# M109X.net
KiCad netlist of a schematic drawn in EAGLE
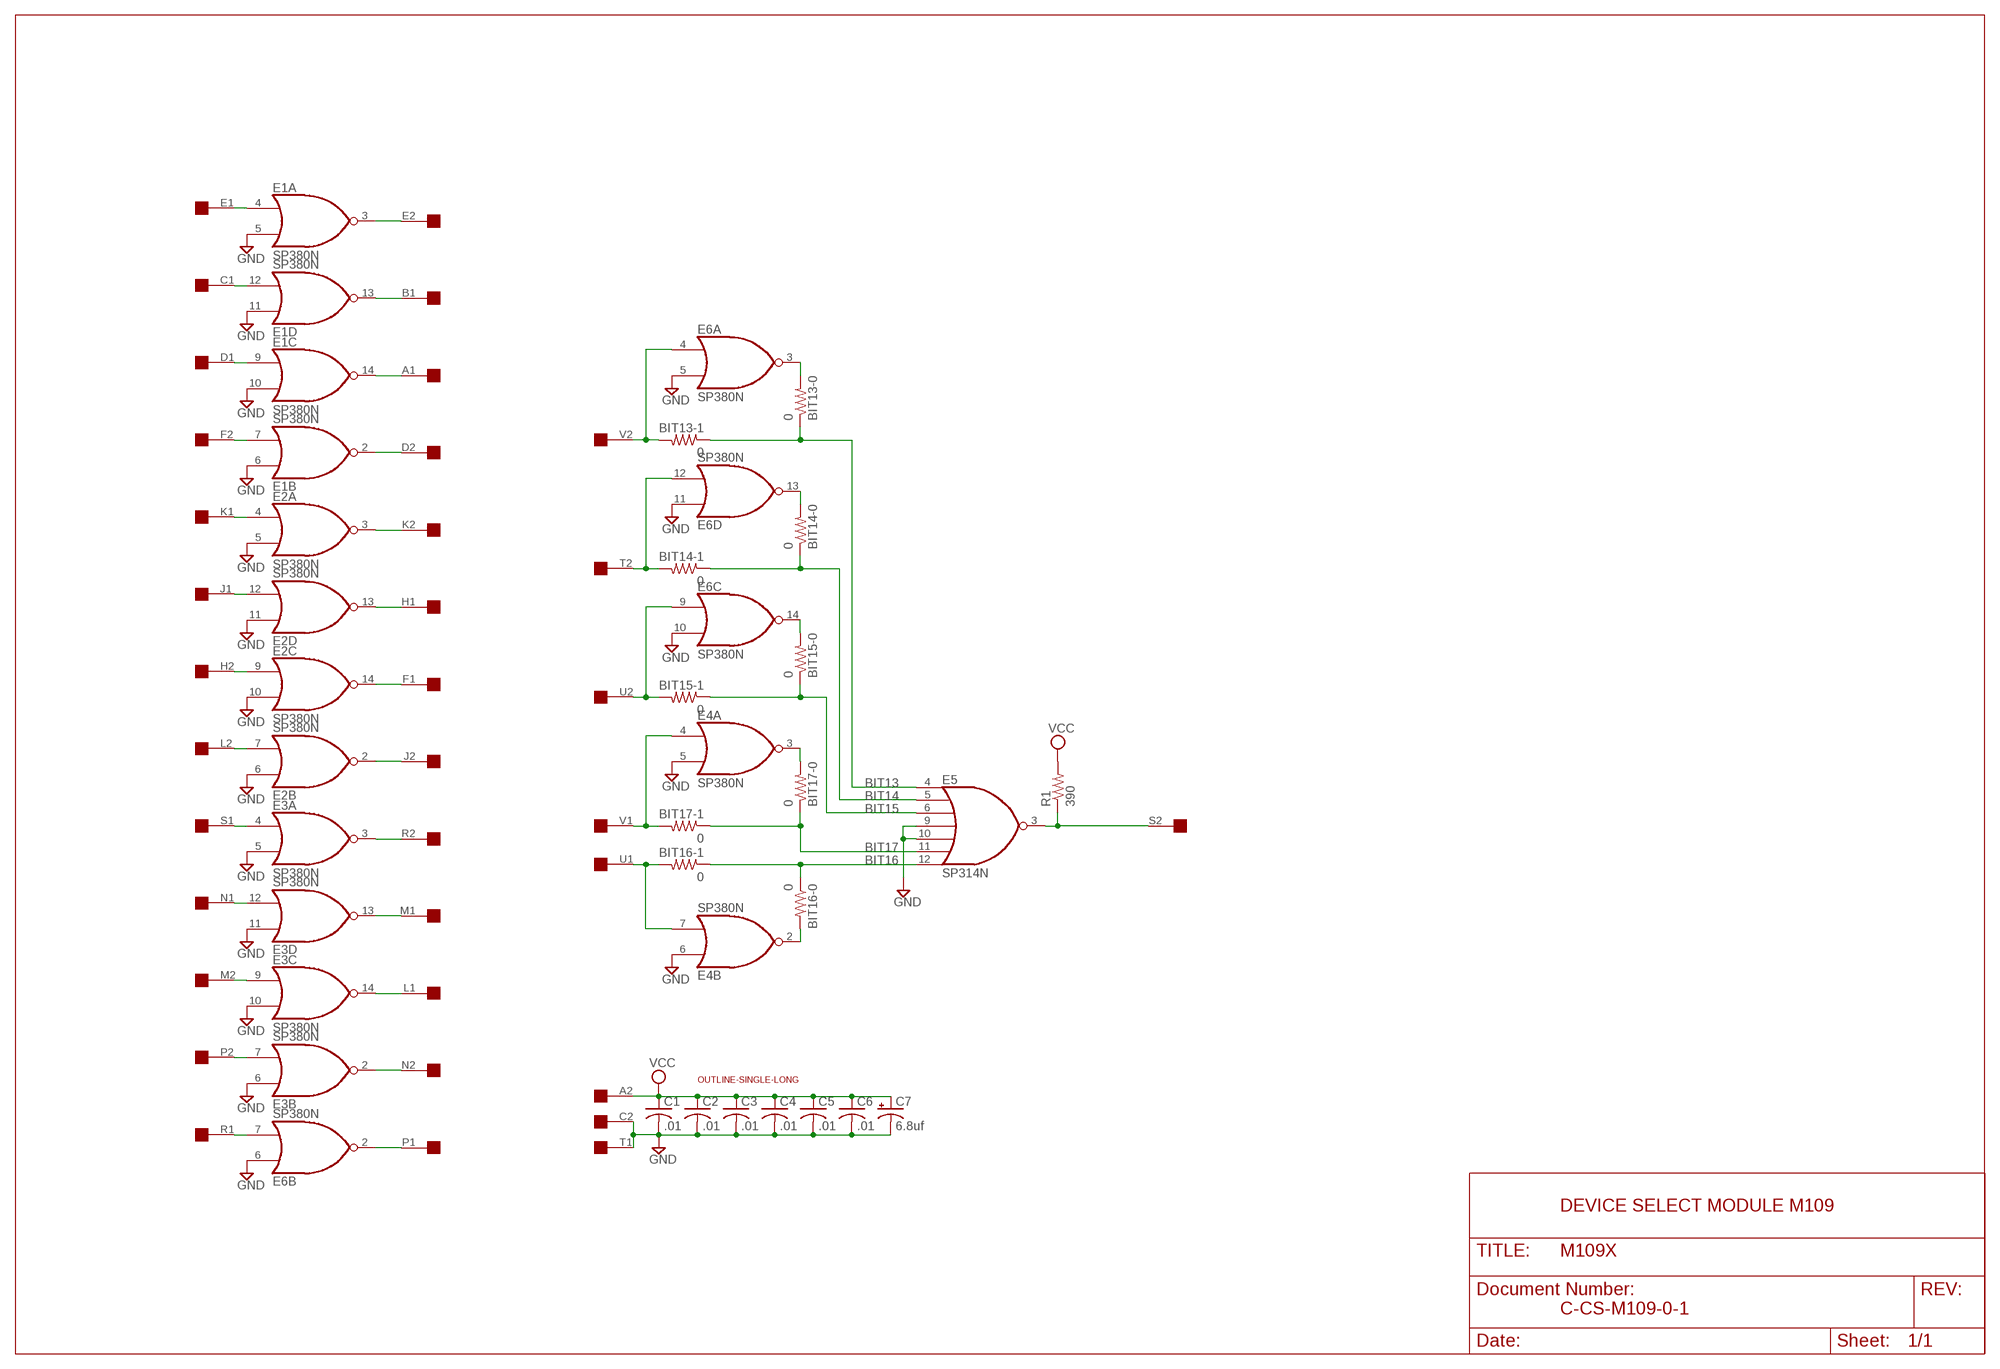
[diagram p0: schematic, sheet 1]

(export (version "E")
  (design (tool "Eeschema 10.0.6"))
  (components
    (comp (ref "BIT13-0")
      (value "0")
      (footprint "eagle-import:0207_10")
      (libsource (lib "eagle-import") (part "R-US_0207/10"))
    )
    (comp (ref "BIT13-1")
      (value "0")
      (footprint "eagle-import:0207_10")
      (libsource (lib "eagle-import") (part "R-US_0207/10"))
    )
    (comp (ref "BIT14-0")
      (value "0")
      (footprint "eagle-import:0207_10")
      (libsource (lib "eagle-import") (part "R-US_0207/10"))
    )
    (comp (ref "BIT14-1")
      (value "0")
      (footprint "eagle-import:0207_10")
      (libsource (lib "eagle-import") (part "R-US_0207/10"))
    )
    (comp (ref "BIT15-0")
      (value "0")
      (footprint "eagle-import:0207_10")
      (libsource (lib "eagle-import") (part "R-US_0207/10"))
    )
    (comp (ref "BIT15-1")
      (value "0")
      (footprint "eagle-import:0207_10")
      (libsource (lib "eagle-import") (part "R-US_0207/10"))
    )
    (comp (ref "BIT16-0")
      (value "0")
      (footprint "eagle-import:0207_10")
      (libsource (lib "eagle-import") (part "R-US_0207/10"))
    )
    (comp (ref "BIT16-1")
      (value "0")
      (footprint "eagle-import:0207_10")
      (libsource (lib "eagle-import") (part "R-US_0207/10"))
    )
    (comp (ref "BIT17-0")
      (value "0")
      (footprint "eagle-import:0207_10")
      (libsource (lib "eagle-import") (part "R-US_0207/10"))
    )
    (comp (ref "BIT17-1")
      (value "0")
      (footprint "eagle-import:0207_10")
      (libsource (lib "eagle-import") (part "R-US_0207/10"))
    )
    (comp (ref "C1")
      (value ".01")
      (footprint "eagle-import:C050-025X075")
      (libsource (lib "eagle-import") (part "C-US050-025X075"))
    )
    (comp (ref "C2")
      (value ".01")
      (footprint "eagle-import:C050-025X075")
      (libsource (lib "eagle-import") (part "C-US050-025X075"))
    )
    (comp (ref "C3")
      (value ".01")
      (footprint "eagle-import:C050-025X075")
      (libsource (lib "eagle-import") (part "C-US050-025X075"))
    )
    (comp (ref "C4")
      (value ".01")
      (footprint "eagle-import:C050-025X075")
      (libsource (lib "eagle-import") (part "C-US050-025X075"))
    )
    (comp (ref "C5")
      (value ".01")
      (footprint "eagle-import:C050-025X075")
      (libsource (lib "eagle-import") (part "C-US050-025X075"))
    )
    (comp (ref "C6")
      (value ".01")
      (footprint "eagle-import:C050-025X075")
      (libsource (lib "eagle-import") (part "C-US050-025X075"))
    )
    (comp (ref "C7")
      (value "6.8uf")
      (footprint "eagle-import:E22-6")
      (libsource (lib "eagle-import") (part "CPOL-USE22-6AXIAL"))
    )
    (comp (ref "E1")
      (value "SP380N")
      (footprint "eagle-import:DIL14")
      (libsource (lib "eagle-import") (part "SP380N"))
    )
    (comp (ref "E2")
      (value "SP380N")
      (footprint "eagle-import:DIL14")
      (libsource (lib "eagle-import") (part "SP380N"))
    )
    (comp (ref "E3")
      (value "SP380N")
      (footprint "eagle-import:DIL14")
      (libsource (lib "eagle-import") (part "SP380N"))
    )
    (comp (ref "E4")
      (value "SP380N")
      (footprint "eagle-import:DIL14")
      (libsource (lib "eagle-import") (part "SP380N"))
    )
    (comp (ref "E5")
      (value "SP314N")
      (footprint "eagle-import:DIL14")
      (libsource (lib "eagle-import") (part "SP314N"))
    )
    (comp (ref "E6")
      (value "SP380N")
      (footprint "eagle-import:DIL14")
      (libsource (lib "eagle-import") (part "SP380N"))
    )
    (comp (ref "R1")
      (value "390")
      (footprint "eagle-import:0207_10")
      (libsource (lib "eagle-import") (part "R-US_0207/10"))
    )
    (comp (ref "U$1")
      (value "SINGLE")
      (footprint "eagle-import:EDGE-CON2")
      (libsource (lib "eagle-import") (part "SINGLE"))
    )
    (comp (ref "U$2")
      (value "OUTLINE-SINGLE-LONG")
      (footprint "eagle-import:SINGLE-LONG")
      (libsource (lib "eagle-import") (part "OUTLINE-SINGLE-LONG"))
    )
  )
  (nets
    (net (code "1") (name "/BIT13") (class "Default")
      (node (ref "BIT13-0") (pin "1") (pinfunction "1_1") (pintype "passive"))
      (node (ref "BIT13-1") (pin "1") (pinfunction "1_1") (pintype "passive"))
      (node (ref "E5") (pin "4") (pinfunction "I0_4") (pintype "input"))
    )
    (net (code "2") (name "/BIT14") (class "Default")
      (node (ref "BIT14-0") (pin "1") (pinfunction "1_1") (pintype "passive"))
      (node (ref "BIT14-1") (pin "1") (pinfunction "1_1") (pintype "passive"))
      (node (ref "E5") (pin "5") (pinfunction "I1_5") (pintype "input"))
    )
    (net (code "3") (name "/BIT15") (class "Default")
      (node (ref "BIT15-0") (pin "1") (pinfunction "1_1") (pintype "passive"))
      (node (ref "BIT15-1") (pin "1") (pinfunction "1_1") (pintype "passive"))
      (node (ref "E5") (pin "6") (pinfunction "I2_6") (pintype "input"))
    )
    (net (code "4") (name "/BIT16") (class "Default")
      (node (ref "BIT16-0") (pin "1") (pinfunction "1_1") (pintype "passive"))
      (node (ref "BIT16-1") (pin "1") (pinfunction "1_1") (pintype "passive"))
      (node (ref "E5") (pin "12") (pinfunction "I6_12") (pintype "input"))
    )
    (net (code "5") (name "/BIT17") (class "Default")
      (node (ref "BIT17-0") (pin "1") (pinfunction "1_1") (pintype "passive"))
      (node (ref "BIT17-1") (pin "1") (pinfunction "1_1") (pintype "passive"))
      (node (ref "E5") (pin "11") (pinfunction "I5_11") (pintype "input"))
    )
    (net (code "6") (name "GND") (class "Default")
      (node (ref "C1") (pin "2") (pinfunction "2_2") (pintype "passive"))
      (node (ref "C2") (pin "2") (pinfunction "2_2") (pintype "passive"))
      (node (ref "C3") (pin "2") (pinfunction "2_2") (pintype "passive"))
      (node (ref "C4") (pin "2") (pinfunction "2_2") (pintype "passive"))
      (node (ref "C5") (pin "2") (pinfunction "2_2") (pintype "passive"))
      (node (ref "C6") (pin "2") (pinfunction "2_2") (pintype "passive"))
      (node (ref "C7") (pin "-") (pinfunction "-_-") (pintype "passive"))
      (node (ref "E1") (pin "10") (pinfunction "I1_10") (pintype "input"))
      (node (ref "E1") (pin "11") (pinfunction "I0_11") (pintype "input"))
      (node (ref "E1") (pin "5") (pinfunction "I1_5") (pintype "input"))
      (node (ref "E1") (pin "6") (pinfunction "I0_6") (pintype "input"))
      (node (ref "E2") (pin "10") (pinfunction "I1_10") (pintype "input"))
      (node (ref "E2") (pin "11") (pinfunction "I0_11") (pintype "input"))
      (node (ref "E2") (pin "5") (pinfunction "I1_5") (pintype "input"))
      (node (ref "E2") (pin "6") (pinfunction "I0_6") (pintype "input"))
      (node (ref "E3") (pin "10") (pinfunction "I1_10") (pintype "input"))
      (node (ref "E3") (pin "11") (pinfunction "I0_11") (pintype "input"))
      (node (ref "E3") (pin "5") (pinfunction "I1_5") (pintype "input"))
      (node (ref "E3") (pin "6") (pinfunction "I0_6") (pintype "input"))
      (node (ref "E4") (pin "5") (pinfunction "I1_5") (pintype "input"))
      (node (ref "E4") (pin "6") (pinfunction "I0_6") (pintype "input"))
      (node (ref "E5") (pin "10") (pinfunction "I4_10") (pintype "input"))
      (node (ref "E5") (pin "9") (pinfunction "I3_9") (pintype "input"))
      (node (ref "E6") (pin "10") (pinfunction "I1_10") (pintype "input"))
      (node (ref "E6") (pin "11") (pinfunction "I0_11") (pintype "input"))
      (node (ref "E6") (pin "5") (pinfunction "I1_5") (pintype "input"))
      (node (ref "E6") (pin "6") (pinfunction "I0_6") (pintype "input"))
      (node (ref "U$1") (pin "C2") (pinfunction "1_C2") (pintype "bidirectional"))
      (node (ref "U$1") (pin "T1") (pinfunction "1_T1") (pintype "bidirectional"))
    )
    (net (code "7") (name "Net-(E1A-I0)") (class "Default")
      (node (ref "E1") (pin "4") (pinfunction "I0_4") (pintype "input"))
      (node (ref "U$1") (pin "E1") (pinfunction "1_E1") (pintype "bidirectional"))
    )
    (net (code "8") (name "Net-(E1A-O)") (class "Default")
      (node (ref "E1") (pin "3") (pinfunction "O_3") (pintype "output"))
      (node (ref "U$1") (pin "E2") (pinfunction "1_E2") (pintype "bidirectional"))
    )
    (net (code "9") (name "Net-(E1B-I1)") (class "Default")
      (node (ref "E1") (pin "7") (pinfunction "I1_7") (pintype "input"))
      (node (ref "U$1") (pin "F2") (pinfunction "1_F2") (pintype "bidirectional"))
    )
    (net (code "10") (name "Net-(E1B-O)") (class "Default")
      (node (ref "E1") (pin "2") (pinfunction "O_2") (pintype "output"))
      (node (ref "U$1") (pin "D2") (pinfunction "1_D2") (pintype "bidirectional"))
    )
    (net (code "11") (name "Net-(E1C-I0)") (class "Default")
      (node (ref "E1") (pin "9") (pinfunction "I0_9") (pintype "input"))
      (node (ref "U$1") (pin "D1") (pinfunction "1_D1") (pintype "bidirectional"))
    )
    (net (code "12") (name "Net-(E1C-O)") (class "Default")
      (node (ref "E1") (pin "14") (pinfunction "O_14") (pintype "output"))
      (node (ref "U$1") (pin "A1") (pinfunction "1_A1") (pintype "bidirectional"))
    )
    (net (code "13") (name "Net-(E1D-I1)") (class "Default")
      (node (ref "E1") (pin "12") (pinfunction "I1_12") (pintype "input"))
      (node (ref "U$1") (pin "C1") (pinfunction "1_C1") (pintype "bidirectional"))
    )
    (net (code "14") (name "Net-(E1D-O)") (class "Default")
      (node (ref "E1") (pin "13") (pinfunction "O_13") (pintype "output"))
      (node (ref "U$1") (pin "B1") (pinfunction "1_B1") (pintype "bidirectional"))
    )
    (net (code "15") (name "Net-(E2A-I0)") (class "Default")
      (node (ref "E2") (pin "4") (pinfunction "I0_4") (pintype "input"))
      (node (ref "U$1") (pin "K1") (pinfunction "1_K1") (pintype "bidirectional"))
    )
    (net (code "16") (name "Net-(E2A-O)") (class "Default")
      (node (ref "E2") (pin "3") (pinfunction "O_3") (pintype "output"))
      (node (ref "U$1") (pin "K2") (pinfunction "1_K2") (pintype "bidirectional"))
    )
    (net (code "17") (name "Net-(E2B-I1)") (class "Default")
      (node (ref "E2") (pin "7") (pinfunction "I1_7") (pintype "input"))
      (node (ref "U$1") (pin "L2") (pinfunction "1_L2") (pintype "bidirectional"))
    )
    (net (code "18") (name "Net-(E2B-O)") (class "Default")
      (node (ref "E2") (pin "2") (pinfunction "O_2") (pintype "output"))
      (node (ref "U$1") (pin "J2") (pinfunction "1_J2") (pintype "bidirectional"))
    )
    (net (code "19") (name "Net-(E2C-I0)") (class "Default")
      (node (ref "E2") (pin "9") (pinfunction "I0_9") (pintype "input"))
      (node (ref "U$1") (pin "H2") (pinfunction "1_H2") (pintype "bidirectional"))
    )
    (net (code "20") (name "Net-(E2C-O)") (class "Default")
      (node (ref "E2") (pin "14") (pinfunction "O_14") (pintype "output"))
      (node (ref "U$1") (pin "F1") (pinfunction "1_F1") (pintype "bidirectional"))
    )
    (net (code "21") (name "Net-(E2D-I1)") (class "Default")
      (node (ref "E2") (pin "12") (pinfunction "I1_12") (pintype "input"))
      (node (ref "U$1") (pin "J1") (pinfunction "1_J1") (pintype "bidirectional"))
    )
    (net (code "22") (name "Net-(E2D-O)") (class "Default")
      (node (ref "E2") (pin "13") (pinfunction "O_13") (pintype "output"))
      (node (ref "U$1") (pin "H1") (pinfunction "1_H1") (pintype "bidirectional"))
    )
    (net (code "23") (name "Net-(E3A-I0)") (class "Default")
      (node (ref "E3") (pin "4") (pinfunction "I0_4") (pintype "input"))
      (node (ref "U$1") (pin "S1") (pinfunction "1_S1") (pintype "bidirectional"))
    )
    (net (code "24") (name "Net-(E3A-O)") (class "Default")
      (node (ref "E3") (pin "3") (pinfunction "O_3") (pintype "output"))
      (node (ref "U$1") (pin "R2") (pinfunction "1_R2") (pintype "bidirectional"))
    )
    (net (code "25") (name "Net-(E3B-I1)") (class "Default")
      (node (ref "E3") (pin "7") (pinfunction "I1_7") (pintype "input"))
      (node (ref "U$1") (pin "P2") (pinfunction "1_P2") (pintype "bidirectional"))
    )
    (net (code "26") (name "Net-(E3B-O)") (class "Default")
      (node (ref "E3") (pin "2") (pinfunction "O_2") (pintype "output"))
      (node (ref "U$1") (pin "N2") (pinfunction "1_N2") (pintype "bidirectional"))
    )
    (net (code "27") (name "Net-(E3C-I0)") (class "Default")
      (node (ref "E3") (pin "9") (pinfunction "I0_9") (pintype "input"))
      (node (ref "U$1") (pin "M2") (pinfunction "1_M2") (pintype "bidirectional"))
    )
    (net (code "28") (name "Net-(E3C-O)") (class "Default")
      (node (ref "E3") (pin "14") (pinfunction "O_14") (pintype "output"))
      (node (ref "U$1") (pin "L1") (pinfunction "1_L1") (pintype "bidirectional"))
    )
    (net (code "29") (name "Net-(E3D-I1)") (class "Default")
      (node (ref "E3") (pin "12") (pinfunction "I1_12") (pintype "input"))
      (node (ref "U$1") (pin "N1") (pinfunction "1_N1") (pintype "bidirectional"))
    )
    (net (code "30") (name "Net-(E3D-O)") (class "Default")
      (node (ref "E3") (pin "13") (pinfunction "O_13") (pintype "output"))
      (node (ref "U$1") (pin "M1") (pinfunction "1_M1") (pintype "bidirectional"))
    )
    (net (code "31") (name "Net-(E4A-I0)") (class "Default")
      (node (ref "BIT17-1") (pin "2") (pinfunction "2_2") (pintype "passive"))
      (node (ref "E4") (pin "4") (pinfunction "I0_4") (pintype "input"))
      (node (ref "U$1") (pin "V1") (pinfunction "1_V1") (pintype "bidirectional"))
    )
    (net (code "32") (name "Net-(E4A-O)") (class "Default")
      (node (ref "BIT17-0") (pin "2") (pinfunction "2_2") (pintype "passive"))
      (node (ref "E4") (pin "3") (pinfunction "O_3") (pintype "output"))
    )
    (net (code "33") (name "Net-(E4B-I1)") (class "Default")
      (node (ref "BIT16-1") (pin "2") (pinfunction "2_2") (pintype "passive"))
      (node (ref "E4") (pin "7") (pinfunction "I1_7") (pintype "input"))
      (node (ref "U$1") (pin "U1") (pinfunction "1_U1") (pintype "bidirectional"))
    )
    (net (code "34") (name "Net-(E4B-O)") (class "Default")
      (node (ref "BIT16-0") (pin "2") (pinfunction "2_2") (pintype "passive"))
      (node (ref "E4") (pin "2") (pinfunction "O_2") (pintype "output"))
    )
    (net (code "35") (name "Net-(E5A-O)") (class "Default")
      (node (ref "E5") (pin "3") (pinfunction "O_3") (pintype "output"))
      (node (ref "R1") (pin "1") (pinfunction "1_1") (pintype "passive"))
      (node (ref "U$1") (pin "S2") (pinfunction "1_S2") (pintype "bidirectional"))
    )
    (net (code "36") (name "Net-(E6A-I0)") (class "Default")
      (node (ref "BIT13-1") (pin "2") (pinfunction "2_2") (pintype "passive"))
      (node (ref "E6") (pin "4") (pinfunction "I0_4") (pintype "input"))
      (node (ref "U$1") (pin "V2") (pinfunction "1_V2") (pintype "bidirectional"))
    )
    (net (code "37") (name "Net-(E6A-O)") (class "Default")
      (node (ref "BIT13-0") (pin "2") (pinfunction "2_2") (pintype "passive"))
      (node (ref "E6") (pin "3") (pinfunction "O_3") (pintype "output"))
    )
    (net (code "38") (name "Net-(E6B-I1)") (class "Default")
      (node (ref "E6") (pin "7") (pinfunction "I1_7") (pintype "input"))
      (node (ref "U$1") (pin "R1") (pinfunction "1_R1") (pintype "bidirectional"))
    )
    (net (code "39") (name "Net-(E6B-O)") (class "Default")
      (node (ref "E6") (pin "2") (pinfunction "O_2") (pintype "output"))
      (node (ref "U$1") (pin "P1") (pinfunction "1_P1") (pintype "bidirectional"))
    )
    (net (code "40") (name "Net-(E6C-I0)") (class "Default")
      (node (ref "BIT15-1") (pin "2") (pinfunction "2_2") (pintype "passive"))
      (node (ref "E6") (pin "9") (pinfunction "I0_9") (pintype "input"))
      (node (ref "U$1") (pin "U2") (pinfunction "1_U2") (pintype "bidirectional"))
    )
    (net (code "41") (name "Net-(E6C-O)") (class "Default")
      (node (ref "BIT15-0") (pin "2") (pinfunction "2_2") (pintype "passive"))
      (node (ref "E6") (pin "14") (pinfunction "O_14") (pintype "output"))
    )
    (net (code "42") (name "Net-(E6D-I1)") (class "Default")
      (node (ref "BIT14-1") (pin "2") (pinfunction "2_2") (pintype "passive"))
      (node (ref "E6") (pin "12") (pinfunction "I1_12") (pintype "input"))
      (node (ref "U$1") (pin "T2") (pinfunction "1_T2") (pintype "bidirectional"))
    )
    (net (code "43") (name "Net-(E6D-O)") (class "Default")
      (node (ref "BIT14-0") (pin "2") (pinfunction "2_2") (pintype "passive"))
      (node (ref "E6") (pin "13") (pinfunction "O_13") (pintype "output"))
    )
    (net (code "44") (name "VCC") (class "Default")
      (node (ref "C1") (pin "1") (pinfunction "1_1") (pintype "passive"))
      (node (ref "C2") (pin "1") (pinfunction "1_1") (pintype "passive"))
      (node (ref "C3") (pin "1") (pinfunction "1_1") (pintype "passive"))
      (node (ref "C4") (pin "1") (pinfunction "1_1") (pintype "passive"))
      (node (ref "C5") (pin "1") (pinfunction "1_1") (pintype "passive"))
      (node (ref "C6") (pin "1") (pinfunction "1_1") (pintype "passive"))
      (node (ref "C7") (pin "+") (pinfunction "+_+") (pintype "passive"))
      (node (ref "R1") (pin "2") (pinfunction "2_2") (pintype "passive"))
      (node (ref "U$1") (pin "A2") (pinfunction "1_A2") (pintype "bidirectional"))
    )
  )
)
